# BatMeas5_3_JST.net
KiCad netlist of a schematic drawn in EAGLE
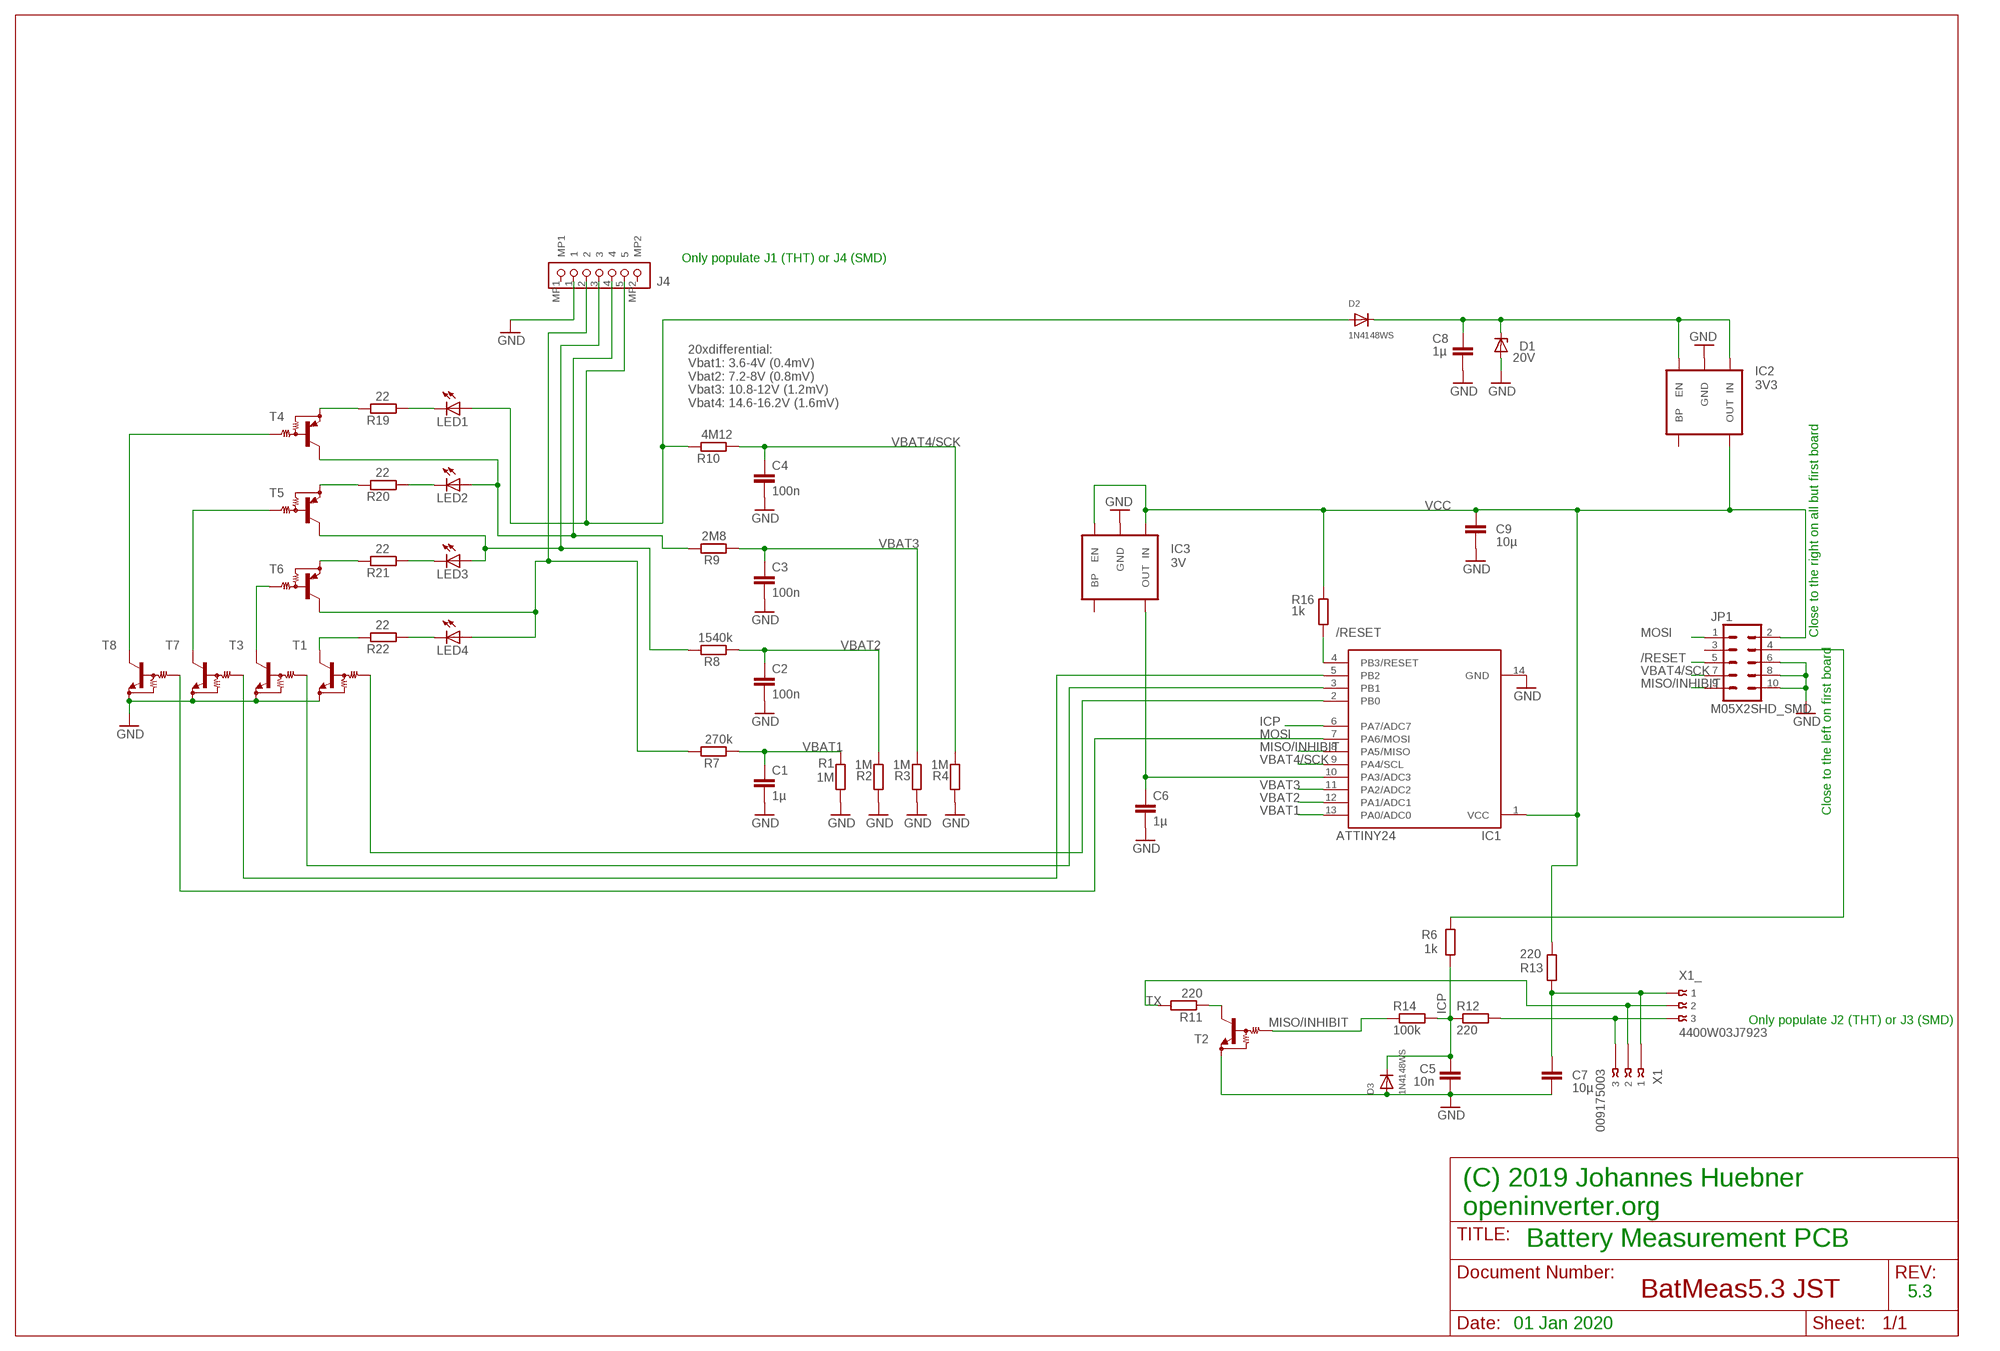
[diagram p0: schematic, sheet 1]

(export (version "E")
  (design (tool "Eeschema 10.0.6"))
  (components
    (comp (ref "C1")
      (value "1µ")
      (footprint "eagle-import:C0603")
      (libsource (lib "eagle-import") (part "C-EUC0603"))
    )
    (comp (ref "C2")
      (value "100n")
      (footprint "eagle-import:C0603")
      (libsource (lib "eagle-import") (part "C-EUC0603"))
    )
    (comp (ref "C3")
      (value "100n")
      (footprint "eagle-import:C0603")
      (libsource (lib "eagle-import") (part "C-EUC0603"))
    )
    (comp (ref "C4")
      (value "100n")
      (footprint "eagle-import:C0603")
      (libsource (lib "eagle-import") (part "C-EUC0603"))
    )
    (comp (ref "C5")
      (value "10n")
      (footprint "eagle-import:C0603")
      (libsource (lib "eagle-import") (part "C-EUC0603"))
    )
    (comp (ref "C6")
      (value "1µ")
      (footprint "eagle-import:C0603")
      (libsource (lib "eagle-import") (part "C-EUC0603"))
    )
    (comp (ref "C7")
      (value "10µ")
      (footprint "eagle-import:C0805")
      (libsource (lib "eagle-import") (part "C-EUC0805"))
    )
    (comp (ref "C8")
      (value "1µ")
      (footprint "eagle-import:C0805")
      (libsource (lib "eagle-import") (part "C-EUC0805"))
    )
    (comp (ref "C9")
      (value "10µ")
      (footprint "eagle-import:C0805")
      (libsource (lib "eagle-import") (part "C-EUC0805"))
    )
    (comp (ref "D1")
      (value "20V")
      (footprint "eagle-import:SMB")
      (libsource (lib "eagle-import") (part "ZENER-DIODESMB"))
    )
    (comp (ref "D2")
      (value "1N4148WS")
      (footprint "eagle-import:SOD-323F")
      (libsource (lib "eagle-import") (part "DIODESOD-323F"))
    )
    (comp (ref "D3")
      (value "1N4148WS")
      (footprint "eagle-import:SOD-323F")
      (libsource (lib "eagle-import") (part "DIODESOD-323F"))
    )
    (comp (ref "IC1")
      (value "ATTINY24")
      (footprint "eagle-import:SO014")
      (libsource (lib "eagle-import") (part "ATTINY24"))
    )
    (comp (ref "IC2")
      (value "3V3")
      (footprint "eagle-import:SOT23-5")
      (libsource (lib "eagle-import") (part "V_REG_LDOSMD"))
    )
    (comp (ref "IC3")
      (value "3V")
      (footprint "eagle-import:SOT23-5")
      (libsource (lib "eagle-import") (part "V_REG_LDOSMD"))
    )
    (comp (ref "J4")
      (value "BM05B-PASS-1-TFT_(LF)(SN)SMD")
      (footprint "eagle-import:BM05BPASS1TFTLFSN")
      (libsource (lib "eagle-import") (part "BM05B-PASS-1-TFT_(LF)(SN)SMD"))
    )
    (comp (ref "JP1")
      (value "M05X2SHD_SMD")
      (footprint "eagle-import:2X5-SHROUDED_SMD")
      (libsource (lib "eagle-import") (part "M05X2SHD_SMD"))
    )
    (comp (ref "LED1")
      (value "150060GS75000")
      (footprint "eagle-import:CHIPLED_0805")
      (libsource (lib "eagle-import") (part "LEDCHIPLED_0805"))
    )
    (comp (ref "LED2")
      (value "150060GS75000")
      (footprint "eagle-import:CHIPLED_0805")
      (libsource (lib "eagle-import") (part "LEDCHIPLED_0805"))
    )
    (comp (ref "LED3")
      (value "150060GS75000")
      (footprint "eagle-import:CHIPLED_0805")
      (libsource (lib "eagle-import") (part "LEDCHIPLED_0805"))
    )
    (comp (ref "LED4")
      (value "150060GS75000")
      (footprint "eagle-import:CHIPLED_0805")
      (libsource (lib "eagle-import") (part "LEDCHIPLED_0805"))
    )
    (comp (ref "R1")
      (value "1M")
      (footprint "eagle-import:R0603")
      (libsource (lib "eagle-import") (part "R-EU_R0603"))
    )
    (comp (ref "R2")
      (value "1M")
      (footprint "eagle-import:R0603")
      (libsource (lib "eagle-import") (part "R-EU_R0603"))
    )
    (comp (ref "R3")
      (value "1M")
      (footprint "eagle-import:R0603")
      (libsource (lib "eagle-import") (part "R-EU_R0603"))
    )
    (comp (ref "R4")
      (value "1M")
      (footprint "eagle-import:R0603")
      (libsource (lib "eagle-import") (part "R-EU_R0603"))
    )
    (comp (ref "R6")
      (value "1k")
      (footprint "eagle-import:R0603")
      (libsource (lib "eagle-import") (part "R-EU_R0603"))
    )
    (comp (ref "R7")
      (value "270k")
      (footprint "eagle-import:R0603")
      (libsource (lib "eagle-import") (part "R-EU_R0603"))
    )
    (comp (ref "R8")
      (value "1540k")
      (footprint "eagle-import:R0603")
      (libsource (lib "eagle-import") (part "R-EU_R0603"))
    )
    (comp (ref "R9")
      (value "2M8")
      (footprint "eagle-import:R0603")
      (libsource (lib "eagle-import") (part "R-EU_R0603"))
    )
    (comp (ref "R10")
      (value "4M12")
      (footprint "eagle-import:R0603")
      (libsource (lib "eagle-import") (part "R-EU_R0603"))
    )
    (comp (ref "R11")
      (value "220")
      (footprint "eagle-import:R0603")
      (libsource (lib "eagle-import") (part "R-EU_R0603"))
    )
    (comp (ref "R12")
      (value "220")
      (footprint "eagle-import:R0603")
      (libsource (lib "eagle-import") (part "R-EU_R0603"))
    )
    (comp (ref "R13")
      (value "220")
      (footprint "eagle-import:R0603")
      (libsource (lib "eagle-import") (part "R-EU_R0603"))
    )
    (comp (ref "R14")
      (value "100k")
      (footprint "eagle-import:R0603")
      (libsource (lib "eagle-import") (part "R-EU_R0603"))
    )
    (comp (ref "R16")
      (value "1k")
      (footprint "eagle-import:R0603")
      (libsource (lib "eagle-import") (part "R-EU_R0603"))
    )
    (comp (ref "R19")
      (value "22")
      (footprint "eagle-import:R0805")
      (libsource (lib "eagle-import") (part "R-EU_R0805"))
    )
    (comp (ref "R20")
      (value "22")
      (footprint "eagle-import:R0805")
      (libsource (lib "eagle-import") (part "R-EU_R0805"))
    )
    (comp (ref "R21")
      (value "22")
      (footprint "eagle-import:R0805")
      (libsource (lib "eagle-import") (part "R-EU_R0805"))
    )
    (comp (ref "R22")
      (value "22")
      (footprint "eagle-import:R0805")
      (libsource (lib "eagle-import") (part "R-EU_R0805"))
    )
    (comp (ref "T1")
      (value "MMUN2233")
      (footprint "eagle-import:SC59-BEC")
      (libsource (lib "eagle-import") (part "-NPN_DRIVER-SC59-BECMUN2211T1"))
    )
    (comp (ref "T2")
      (value "MMUN2233")
      (footprint "eagle-import:SC59-BEC")
      (libsource (lib "eagle-import") (part "-NPN_DRIVER-SC59-BECMUN2211T1"))
    )
    (comp (ref "T3")
      (value "MMUN2233")
      (footprint "eagle-import:SC59-BEC")
      (libsource (lib "eagle-import") (part "-NPN_DRIVER-SC59-BECMUN2211T1"))
    )
    (comp (ref "T4")
      (value "MMUN2111LT1G")
      (footprint "eagle-import:SC59-BEC")
      (libsource (lib "eagle-import") (part "-PNP_DRIVER-SC59-BECMUN2111T1"))
    )
    (comp (ref "T5")
      (value "MMUN2111LT1G")
      (footprint "eagle-import:SC59-BEC")
      (libsource (lib "eagle-import") (part "-PNP_DRIVER-SC59-BECMUN2111T1"))
    )
    (comp (ref "T6")
      (value "MMUN2111LT1G")
      (footprint "eagle-import:SC59-BEC")
      (libsource (lib "eagle-import") (part "-PNP_DRIVER-SC59-BECMUN2111T1"))
    )
    (comp (ref "T7")
      (value "MMUN2233")
      (footprint "eagle-import:SC59-BEC")
      (libsource (lib "eagle-import") (part "-NPN_DRIVER-SC59-BECMUN2211T1"))
    )
    (comp (ref "T8")
      (value "MMUN2233")
      (footprint "eagle-import:SC59-BEC")
      (libsource (lib "eagle-import") (part "-NPN_DRIVER-SC59-BECMUN2211T1"))
    )
    (comp (ref "X1")
      (value "009175003")
      (footprint "eagle-import:009175003")
      (fields (field (name "MPN") "009175003001006"))
      (libsource (lib "eagle-import") (part "009175003"))
    )
    (comp (ref "X1_")
      (value "4400W03J7923")
      (footprint "eagle-import:4400WXXJ7923")
      (libsource (lib "eagle-import") (part "4400W03J7923"))
    )
  )
  (nets
    (net (code "1") (name "/ICP") (class "Default")
      (node (ref "C5") (pin "1") (pinfunction "1_1") (pintype "passive"))
      (node (ref "D3") (pin "C") (pinfunction "C_C") (pintype "passive"))
      (node (ref "IC1") (pin "6") (pinfunction "PA7/ADC7_6") (pintype "bidirectional"))
      (node (ref "R12") (pin "1") (pinfunction "1_1") (pintype "passive"))
      (node (ref "R14") (pin "2") (pinfunction "2_2") (pintype "passive"))
      (node (ref "R6") (pin "1") (pinfunction "1_1") (pintype "passive"))
    )
    (net (code "2") (name "/MISO{slash}INHIBIT") (class "Default")
      (node (ref "IC1") (pin "8") (pinfunction "PA5/MISO_8") (pintype "bidirectional"))
      (node (ref "JP1") (pin "9") (pinfunction "9_9") (pintype "passive"))
      (node (ref "R14") (pin "1") (pinfunction "1_1") (pintype "passive"))
      (node (ref "T2") (pin "B") (pinfunction "B_B") (pintype "passive"))
    )
    (net (code "3") (name "/MOSI") (class "Default")
      (node (ref "IC1") (pin "7") (pinfunction "PA6/MOSI_7") (pintype "bidirectional"))
      (node (ref "JP1") (pin "1") (pinfunction "1_1") (pintype "passive"))
      (node (ref "T8") (pin "B") (pinfunction "B_B") (pintype "passive"))
    )
    (net (code "4") (name "/TX") (class "Default")
      (node (ref "R11") (pin "2") (pinfunction "2_2") (pintype "passive"))
      (node (ref "X1") (pin "2@1") (pinfunction "2_2@1") (pintype "passive"))
      (node (ref "X1_") (pin "P$2") (pinfunction "2_P$2") (pintype "passive"))
    )
    (net (code "5") (name "/VBAT1") (class "Default")
      (node (ref "C1") (pin "1") (pinfunction "1_1") (pintype "passive"))
      (node (ref "IC1") (pin "13") (pinfunction "PA0/ADC0_13") (pintype "bidirectional"))
      (node (ref "R1") (pin "1") (pinfunction "1_1") (pintype "passive"))
      (node (ref "R7") (pin "1") (pinfunction "1_1") (pintype "passive"))
    )
    (net (code "6") (name "/VBAT2") (class "Default")
      (node (ref "C2") (pin "1") (pinfunction "1_1") (pintype "passive"))
      (node (ref "IC1") (pin "12") (pinfunction "PA1/ADC1_12") (pintype "bidirectional"))
      (node (ref "R2") (pin "1") (pinfunction "1_1") (pintype "passive"))
      (node (ref "R8") (pin "1") (pinfunction "1_1") (pintype "passive"))
    )
    (net (code "7") (name "/VBAT3") (class "Default")
      (node (ref "C3") (pin "1") (pinfunction "1_1") (pintype "passive"))
      (node (ref "IC1") (pin "11") (pinfunction "PA2/ADC2_11") (pintype "bidirectional"))
      (node (ref "R3") (pin "1") (pinfunction "1_1") (pintype "passive"))
      (node (ref "R9") (pin "1") (pinfunction "1_1") (pintype "passive"))
    )
    (net (code "8") (name "/VBAT4{slash}SCK") (class "Default")
      (node (ref "C4") (pin "1") (pinfunction "1_1") (pintype "passive"))
      (node (ref "IC1") (pin "9") (pinfunction "PA4/SCL_9") (pintype "bidirectional"))
      (node (ref "JP1") (pin "7") (pinfunction "7_7") (pintype "passive"))
      (node (ref "R10") (pin "1") (pinfunction "1_1") (pintype "passive"))
      (node (ref "R4") (pin "1") (pinfunction "1_1") (pintype "passive"))
    )
    (net (code "9") (name "/VCC") (class "Default")
      (node (ref "C9") (pin "1") (pinfunction "1_1") (pintype "passive"))
      (node (ref "IC1") (pin "1") (pinfunction "VCC_1") (pintype "bidirectional"))
      (node (ref "IC2") (pin "5") (pinfunction "OUT_5") (pintype "passive"))
      (node (ref "IC3") (pin "1") (pinfunction "IN_1") (pintype "input"))
      (node (ref "IC3") (pin "3") (pinfunction "EN_3") (pintype "input"))
      (node (ref "JP1") (pin "2") (pinfunction "2_2") (pintype "passive"))
      (node (ref "R13") (pin "1") (pinfunction "1_1") (pintype "passive"))
      (node (ref "R16") (pin "1") (pinfunction "1_1") (pintype "passive"))
    )
    (net (code "10") (name "/{slash}RESET") (class "Default")
      (node (ref "IC1") (pin "4") (pinfunction "PB3/RESET_4") (pintype "bidirectional"))
      (node (ref "JP1") (pin "5") (pinfunction "5_5") (pintype "passive"))
      (node (ref "R16") (pin "2") (pinfunction "2_2") (pintype "passive"))
    )
    (net (code "11") (name "GND") (class "Default")
      (node (ref "C1") (pin "2") (pinfunction "2_2") (pintype "passive"))
      (node (ref "C2") (pin "2") (pinfunction "2_2") (pintype "passive"))
      (node (ref "C3") (pin "2") (pinfunction "2_2") (pintype "passive"))
      (node (ref "C4") (pin "2") (pinfunction "2_2") (pintype "passive"))
      (node (ref "C5") (pin "2") (pinfunction "2_2") (pintype "passive"))
      (node (ref "C6") (pin "2") (pinfunction "2_2") (pintype "passive"))
      (node (ref "C7") (pin "2") (pinfunction "2_2") (pintype "passive"))
      (node (ref "C8") (pin "2") (pinfunction "2_2") (pintype "passive"))
      (node (ref "C9") (pin "2") (pinfunction "2_2") (pintype "passive"))
      (node (ref "D1") (pin "A") (pinfunction "A_A") (pintype "passive"))
      (node (ref "D3") (pin "A") (pinfunction "A_A") (pintype "passive"))
      (node (ref "IC1") (pin "14") (pinfunction "GND_14") (pintype "bidirectional"))
      (node (ref "IC2") (pin "2") (pinfunction "GND_2") (pintype "input"))
      (node (ref "IC3") (pin "2") (pinfunction "GND_2") (pintype "input"))
      (node (ref "J4") (pin "1") (pinfunction "1_1") (pintype "bidirectional"))
      (node (ref "JP1") (pin "10") (pinfunction "10_10") (pintype "passive"))
      (node (ref "JP1") (pin "6") (pinfunction "6_6") (pintype "passive"))
      (node (ref "JP1") (pin "8") (pinfunction "8_8") (pintype "passive"))
      (node (ref "R1") (pin "2") (pinfunction "2_2") (pintype "passive"))
      (node (ref "R2") (pin "2") (pinfunction "2_2") (pintype "passive"))
      (node (ref "R3") (pin "2") (pinfunction "2_2") (pintype "passive"))
      (node (ref "R4") (pin "2") (pinfunction "2_2") (pintype "passive"))
      (node (ref "T1") (pin "E") (pinfunction "E_E") (pintype "passive"))
      (node (ref "T2") (pin "E") (pinfunction "E_E") (pintype "passive"))
      (node (ref "T3") (pin "E") (pinfunction "E_E") (pintype "passive"))
      (node (ref "T7") (pin "E") (pinfunction "E_E") (pintype "passive"))
      (node (ref "T8") (pin "E") (pinfunction "E_E") (pintype "passive"))
    )
    (net (code "12") (name "Net-(D2-PadA)") (class "Default")
      (node (ref "D2") (pin "A") (pinfunction "A_A") (pintype "passive"))
      (node (ref "J4") (pin "5") (pinfunction "5_5") (pintype "bidirectional"))
      (node (ref "LED1") (pin "A") (pinfunction "A_A") (pintype "passive"))
      (node (ref "R10") (pin "2") (pinfunction "2_2") (pintype "passive"))
    )
    (net (code "13") (name "Net-(IC1-PA3{slash}ADC3)") (class "Default")
      (node (ref "C6") (pin "1") (pinfunction "1_1") (pintype "passive"))
      (node (ref "IC1") (pin "10") (pinfunction "PA3/ADC3_10") (pintype "bidirectional"))
      (node (ref "IC3") (pin "5") (pinfunction "OUT_5") (pintype "passive"))
    )
    (net (code "14") (name "Net-(IC1-PB0)") (class "Default")
      (node (ref "IC1") (pin "2") (pinfunction "PB0_2") (pintype "bidirectional"))
      (node (ref "T1") (pin "B") (pinfunction "B_B") (pintype "passive"))
    )
    (net (code "15") (name "Net-(IC1-PB1)") (class "Default")
      (node (ref "IC1") (pin "3") (pinfunction "PB1_3") (pintype "bidirectional"))
      (node (ref "T3") (pin "B") (pinfunction "B_B") (pintype "passive"))
    )
    (net (code "16") (name "Net-(IC1-PB2)") (class "Default")
      (node (ref "IC1") (pin "5") (pinfunction "PB2_5") (pintype "bidirectional"))
      (node (ref "T7") (pin "B") (pinfunction "B_B") (pintype "passive"))
    )
    (net (code "17") (name "Net-(IC2-EN)") (class "Default")
      (node (ref "C8") (pin "1") (pinfunction "1_1") (pintype "passive"))
      (node (ref "D1") (pin "C") (pinfunction "C_C") (pintype "passive"))
      (node (ref "D2") (pin "C") (pinfunction "C_C") (pintype "passive"))
      (node (ref "IC2") (pin "1") (pinfunction "IN_1") (pintype "input"))
      (node (ref "IC2") (pin "3") (pinfunction "EN_3") (pintype "input"))
    )
    (net (code "18") (name "Net-(J4-Pad2)") (class "Default")
      (node (ref "J4") (pin "2") (pinfunction "2_2") (pintype "bidirectional"))
      (node (ref "LED4") (pin "A") (pinfunction "A_A") (pintype "passive"))
      (node (ref "R7") (pin "2") (pinfunction "2_2") (pintype "passive"))
      (node (ref "T6") (pin "C") (pinfunction "C_C") (pintype "passive"))
    )
    (net (code "19") (name "Net-(J4-Pad3)") (class "Default")
      (node (ref "J4") (pin "3") (pinfunction "3_3") (pintype "bidirectional"))
      (node (ref "LED3") (pin "A") (pinfunction "A_A") (pintype "passive"))
      (node (ref "R8") (pin "2") (pinfunction "2_2") (pintype "passive"))
      (node (ref "T5") (pin "C") (pinfunction "C_C") (pintype "passive"))
    )
    (net (code "20") (name "Net-(J4-Pad4)") (class "Default")
      (node (ref "J4") (pin "4") (pinfunction "4_4") (pintype "bidirectional"))
      (node (ref "LED2") (pin "A") (pinfunction "A_A") (pintype "passive"))
      (node (ref "R9") (pin "2") (pinfunction "2_2") (pintype "passive"))
      (node (ref "T4") (pin "C") (pinfunction "C_C") (pintype "passive"))
    )
    (net (code "21") (name "Net-(JP1-Pad4)") (class "Default")
      (node (ref "JP1") (pin "4") (pinfunction "4_4") (pintype "passive"))
      (node (ref "R6") (pin "2") (pinfunction "2_2") (pintype "passive"))
    )
    (net (code "22") (name "Net-(LED1-PadC)") (class "Default")
      (node (ref "LED1") (pin "C") (pinfunction "C_C") (pintype "passive"))
      (node (ref "R19") (pin "1") (pinfunction "1_1") (pintype "passive"))
    )
    (net (code "23") (name "Net-(LED2-PadC)") (class "Default")
      (node (ref "LED2") (pin "C") (pinfunction "C_C") (pintype "passive"))
      (node (ref "R20") (pin "1") (pinfunction "1_1") (pintype "passive"))
    )
    (net (code "24") (name "Net-(LED3-PadC)") (class "Default")
      (node (ref "LED3") (pin "C") (pinfunction "C_C") (pintype "passive"))
      (node (ref "R21") (pin "1") (pinfunction "1_1") (pintype "passive"))
    )
    (net (code "25") (name "Net-(LED4-PadC)") (class "Default")
      (node (ref "LED4") (pin "C") (pinfunction "C_C") (pintype "passive"))
      (node (ref "R22") (pin "1") (pinfunction "1_1") (pintype "passive"))
    )
    (net (code "26") (name "Net-(R11-Pad1)") (class "Default")
      (node (ref "R11") (pin "1") (pinfunction "1_1") (pintype "passive"))
      (node (ref "T2") (pin "C") (pinfunction "C_C") (pintype "passive"))
    )
    (net (code "27") (name "Net-(R19-Pad2)") (class "Default")
      (node (ref "R19") (pin "2") (pinfunction "2_2") (pintype "passive"))
      (node (ref "T4") (pin "E") (pinfunction "E_E") (pintype "passive"))
    )
    (net (code "28") (name "Net-(R20-Pad2)") (class "Default")
      (node (ref "R20") (pin "2") (pinfunction "2_2") (pintype "passive"))
      (node (ref "T5") (pin "E") (pinfunction "E_E") (pintype "passive"))
    )
    (net (code "29") (name "Net-(R21-Pad2)") (class "Default")
      (node (ref "R21") (pin "2") (pinfunction "2_2") (pintype "passive"))
      (node (ref "T6") (pin "E") (pinfunction "E_E") (pintype "passive"))
    )
    (net (code "30") (name "Net-(R22-Pad2)") (class "Default")
      (node (ref "R22") (pin "2") (pinfunction "2_2") (pintype "passive"))
      (node (ref "T1") (pin "C") (pinfunction "C_C") (pintype "passive"))
    )
    (net (code "31") (name "Net-(T3-PadC)") (class "Default")
      (node (ref "T3") (pin "C") (pinfunction "C_C") (pintype "passive"))
      (node (ref "T6") (pin "B") (pinfunction "B_B") (pintype "passive"))
    )
    (net (code "32") (name "Net-(T4-PadB)") (class "Default")
      (node (ref "T4") (pin "B") (pinfunction "B_B") (pintype "passive"))
      (node (ref "T8") (pin "C") (pinfunction "C_C") (pintype "passive"))
    )
    (net (code "33") (name "Net-(T5-PadB)") (class "Default")
      (node (ref "T5") (pin "B") (pinfunction "B_B") (pintype "passive"))
      (node (ref "T7") (pin "C") (pinfunction "C_C") (pintype "passive"))
    )
    (net (code "34") (name "Net-(X1_-1)") (class "Default")
      (node (ref "C7") (pin "1") (pinfunction "1_1") (pintype "passive"))
      (node (ref "R13") (pin "2") (pinfunction "2_2") (pintype "passive"))
      (node (ref "X1") (pin "1@1") (pinfunction "1_1@1") (pintype "passive"))
      (node (ref "X1_") (pin "P$1") (pinfunction "1_P$1") (pintype "passive"))
    )
    (net (code "35") (name "Net-(X1_-3)") (class "Default")
      (node (ref "R12") (pin "2") (pinfunction "2_2") (pintype "passive"))
      (node (ref "X1") (pin "3@2") (pinfunction "3_3@2") (pintype "passive"))
      (node (ref "X1_") (pin "P$3") (pinfunction "3_P$3") (pintype "passive"))
    )
    (net (code "36") (name "unconnected-(IC2-BP-Pad4)") (class "Default")
      (node (ref "IC2") (pin "4") (pinfunction "BP_4") (pintype "input"))
    )
    (net (code "37") (name "unconnected-(IC3-BP-Pad4)") (class "Default")
      (node (ref "IC3") (pin "4") (pinfunction "BP_4") (pintype "input"))
    )
    (net (code "38") (name "unconnected-(J4-PadMP1)") (class "Default")
      (node (ref "J4") (pin "MP1") (pinfunction "MP1_MP1") (pintype "bidirectional"))
    )
    (net (code "39") (name "unconnected-(J4-PadMP2)") (class "Default")
      (node (ref "J4") (pin "MP2") (pinfunction "MP2_MP2") (pintype "bidirectional"))
    )
    (net (code "40") (name "unconnected-(JP1-Pad3)") (class "Default")
      (node (ref "JP1") (pin "3") (pinfunction "3_3") (pintype "passive"))
    )
    (net (code "41") (name "unconnected-(X1-Pad1)") (class "Default")
      (node (ref "X1") (pin "1") (pinfunction "1_1") (pintype "passive"))
    )
    (net (code "42") (name "unconnected-(X1-Pad2)") (class "Default")
      (node (ref "X1") (pin "2") (pinfunction "2_2") (pintype "passive"))
    )
    (net (code "43") (name "unconnected-(X1-Pad3)") (class "Default")
      (node (ref "X1") (pin "3") (pinfunction "3_3") (pintype "passive"))
    )
  )
)
